# OLED-Display.net
KiCad netlist of a schematic drawn in EAGLE
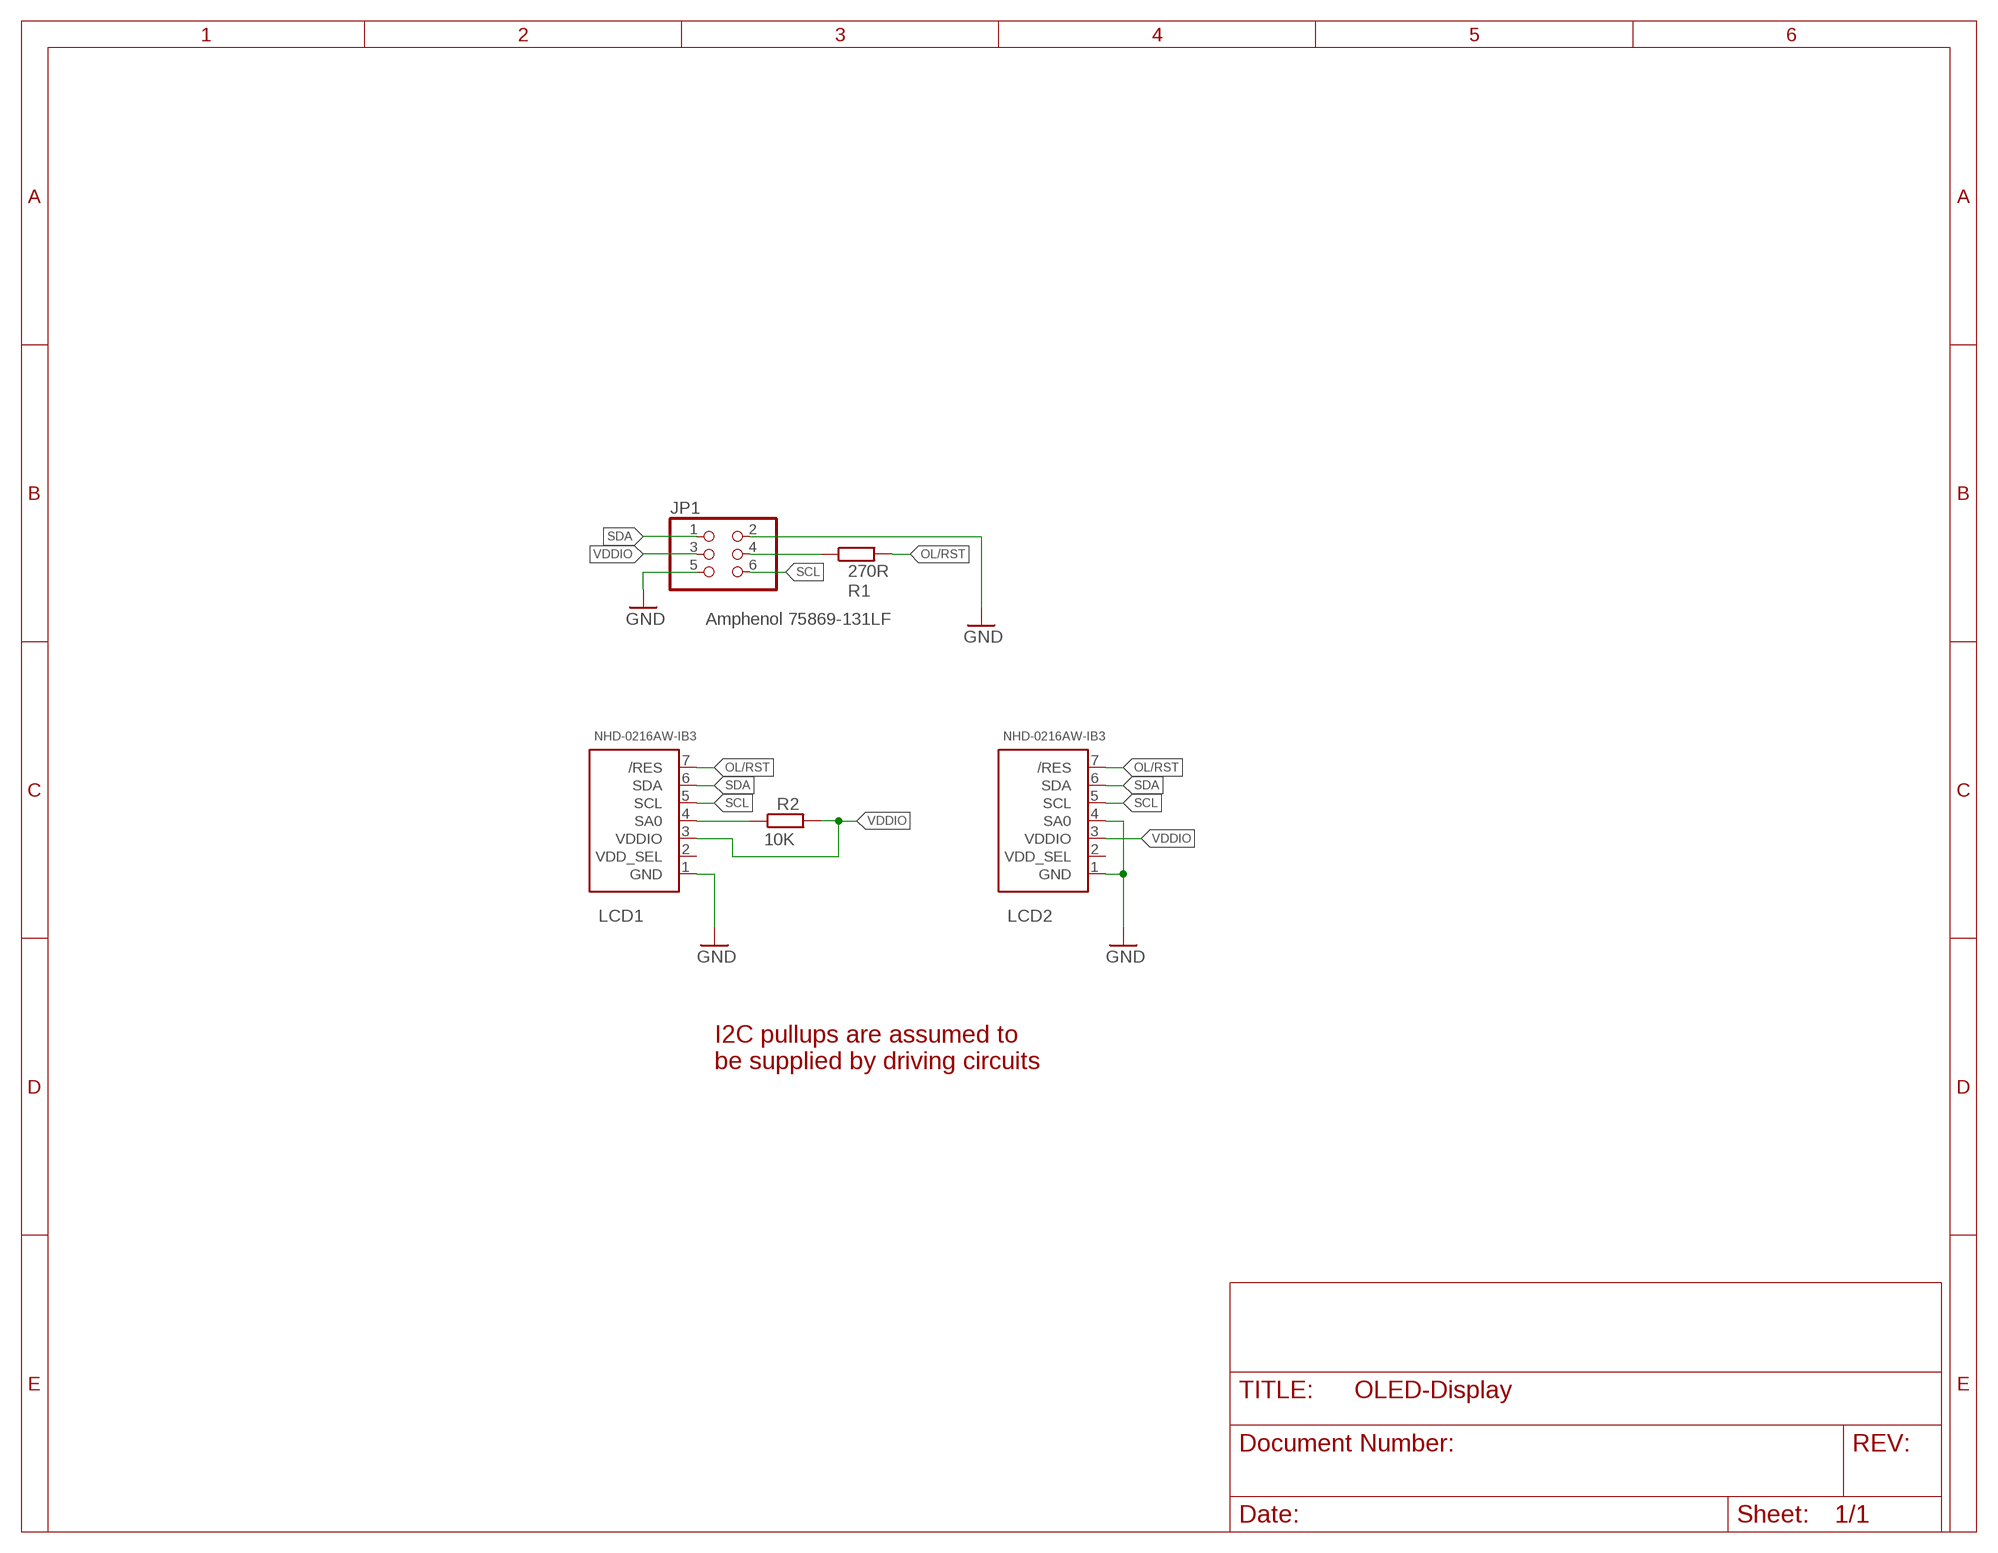
[diagram p0: schematic, sheet 1]

(export (version "E")
  (design (tool "Eeschema 10.0.6"))
  (components
    (comp (ref "JP1")
      (value "Amphenol 75869-131LF")
      (footprint "eagle-import:PINHD-2X3-SHROUDED")
      (libsource (lib "eagle-import") (part "PINHD-2X32X03/SHROUDED"))
    )
    (comp (ref "LCD1")
      (value "NHD-0216AW-IB3")
      (footprint "eagle-import:LCD-NEWHAVEN-16X2")
      (libsource (lib "eagle-import") (part "LCD-NEWHAVEN-16X2"))
    )
    (comp (ref "LCD2")
      (value "NHD-0216AW-IB3")
      (footprint "eagle-import:LCD-NEWHAVEN-16X2")
      (libsource (lib "eagle-import") (part "LCD-NEWHAVEN-16X2"))
    )
    (comp (ref "R1")
      (value "270R")
      (footprint "eagle-import:R0805")
      (libsource (lib "eagle-import") (part "R-EU_R0805"))
    )
    (comp (ref "R2")
      (value "10K")
      (footprint "eagle-import:R0805")
      (libsource (lib "eagle-import") (part "R-EU_R0805"))
    )
  )
  (nets
    (net (code "1") (name "GND") (class "Default")
      (node (ref "JP1") (pin "2") (pinfunction "2_2") (pintype "passive"))
      (node (ref "JP1") (pin "5") (pinfunction "5_5") (pintype "passive"))
      (node (ref "LCD1") (pin "1") (pinfunction "GND_1") (pintype "bidirectional"))
      (node (ref "LCD2") (pin "1") (pinfunction "GND_1") (pintype "bidirectional"))
      (node (ref "LCD2") (pin "4") (pinfunction "SA0_4") (pintype "bidirectional"))
    )
    (net (code "2") (name "Net-(JP1-Pad4)") (class "Default")
      (node (ref "JP1") (pin "4") (pinfunction "4_4") (pintype "passive"))
      (node (ref "R1") (pin "1") (pinfunction "1_1") (pintype "passive"))
    )
    (net (code "3") (name "Net-(LCD1-SA0)") (class "Default")
      (node (ref "LCD1") (pin "4") (pinfunction "SA0_4") (pintype "bidirectional"))
      (node (ref "R2") (pin "1") (pinfunction "1_1") (pintype "passive"))
    )
    (net (code "4") (name "OL{slash}RST") (class "Default")
      (node (ref "LCD1") (pin "7") (pinfunction "/RES_7") (pintype "bidirectional"))
      (node (ref "LCD2") (pin "7") (pinfunction "/RES_7") (pintype "bidirectional"))
      (node (ref "R1") (pin "2") (pinfunction "2_2") (pintype "passive"))
    )
    (net (code "5") (name "SCL") (class "Default")
      (node (ref "JP1") (pin "6") (pinfunction "6_6") (pintype "passive"))
      (node (ref "LCD1") (pin "5") (pinfunction "SCL_5") (pintype "bidirectional"))
      (node (ref "LCD2") (pin "5") (pinfunction "SCL_5") (pintype "bidirectional"))
    )
    (net (code "6") (name "SDA") (class "Default")
      (node (ref "JP1") (pin "1") (pinfunction "1_1") (pintype "passive"))
      (node (ref "LCD1") (pin "6") (pinfunction "SDA_6") (pintype "bidirectional"))
      (node (ref "LCD2") (pin "6") (pinfunction "SDA_6") (pintype "bidirectional"))
    )
    (net (code "7") (name "VDDIO") (class "Default")
      (node (ref "JP1") (pin "3") (pinfunction "3_3") (pintype "passive"))
      (node (ref "LCD1") (pin "3") (pinfunction "VDDIO_3") (pintype "bidirectional"))
      (node (ref "LCD2") (pin "3") (pinfunction "VDDIO_3") (pintype "bidirectional"))
      (node (ref "R2") (pin "2") (pinfunction "2_2") (pintype "passive"))
    )
    (net (code "8") (name "unconnected-(LCD1-VDD_SEL-Pad2)") (class "Default")
      (node (ref "LCD1") (pin "2") (pinfunction "VDD_SEL_2") (pintype "bidirectional"))
    )
    (net (code "9") (name "unconnected-(LCD2-VDD_SEL-Pad2)") (class "Default")
      (node (ref "LCD2") (pin "2") (pinfunction "VDD_SEL_2") (pintype "bidirectional"))
    )
  )
)
